# stokes_polarimeter.net
KiCad netlist of a schematic drawn in EAGLE
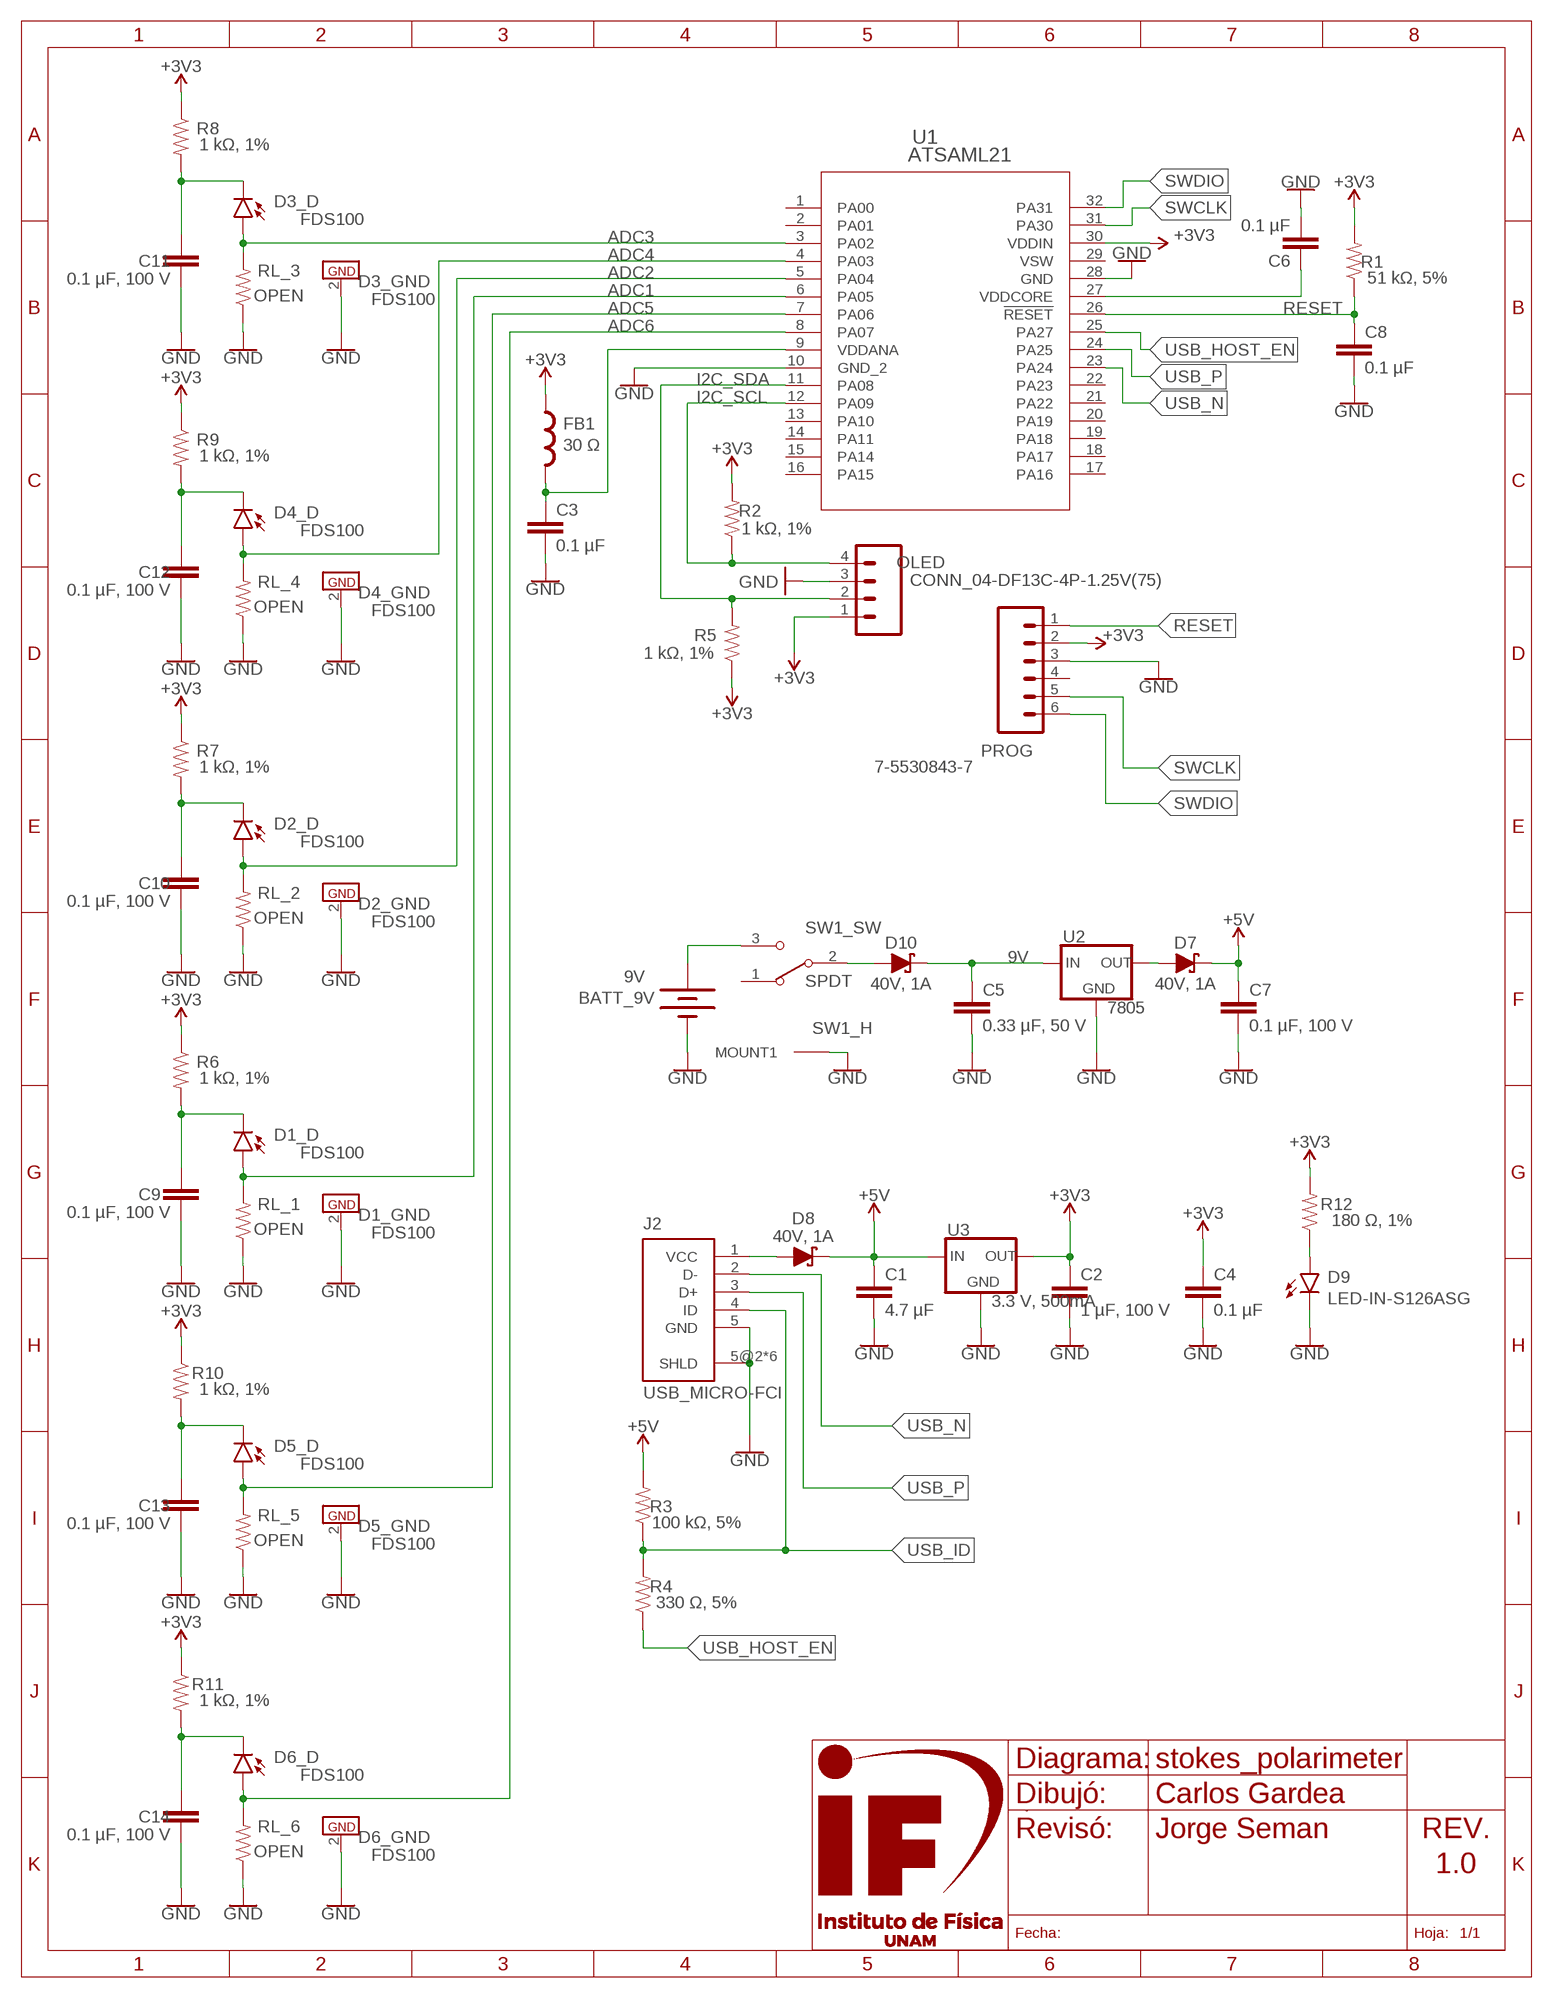
[diagram p0: schematic, sheet 1]

(export (version "E")
  (design (tool "Eeschema 10.0.6"))
  (components
    (comp (ref "BATT_9V")
      (value "9V")
      (footprint "eagle-import:5331")
      (fields (field (name "MFR") "Keystone Electronics"))
      (libsource (lib "eagle-import") (part "9V_BATTERY-5331"))
    )
    (comp (ref "C1")
      (value "4.7 µF")
      (footprint "eagle-import:C1206")
      (fields (field (name "MFR") "KEMET"))
      (libsource (lib "eagle-import") (part "4.7µF-C1206C475K3PACTU"))
    )
    (comp (ref "C2")
      (value "1 µF, 100 V")
      (footprint "eagle-import:C1206")
      (fields (field (name "MFR") "KEMET"))
      (libsource (lib "eagle-import") (part "1µF-C1206X105J1RACTU"))
    )
    (comp (ref "C3")
      (value "0.1 µF")
      (footprint "eagle-import:C1206")
      (fields (field (name "MFR") "KEMET"))
      (libsource (lib "eagle-import") (part "0.1µF-C1206C104J1RACTU"))
    )
    (comp (ref "C4")
      (value "0.1 µF")
      (footprint "eagle-import:C1206")
      (fields (field (name "MFR") "KEMET"))
      (libsource (lib "eagle-import") (part "0.1µF-C1206C104J1RACTU"))
    )
    (comp (ref "C5")
      (value "0.33 µF, 50 V")
      (footprint "eagle-import:C1206")
      (fields (field (name "MFR") "Samsung Electro-Mechanics"))
      (libsource (lib "eagle-import") (part "0.33µF-CL31B334KBFNNNE"))
    )
    (comp (ref "C6")
      (value "0.1 µF")
      (footprint "eagle-import:C1206")
      (fields (field (name "MFR") "KEMET"))
      (libsource (lib "eagle-import") (part "0.1µF-C1206C104J1RACTU"))
    )
    (comp (ref "C7")
      (value "0.1 µF, 100 V")
      (footprint "eagle-import:C1206")
      (fields (field (name "MFR") "AVX"))
      (libsource (lib "eagle-import") (part "0.1µF-12061C104KAT2A"))
    )
    (comp (ref "C8")
      (value "0.1 µF")
      (footprint "eagle-import:C1206")
      (fields (field (name "MFR") "KEMET"))
      (libsource (lib "eagle-import") (part "0.1µF-C1206C104J1RACTU"))
    )
    (comp (ref "C9")
      (value "0.1 µF, 100 V")
      (footprint "eagle-import:C1206")
      (fields (field (name "MFR") "AVX"))
      (libsource (lib "eagle-import") (part "0.1µF-12061C104KAT2A"))
    )
    (comp (ref "C10")
      (value "0.1 µF, 100 V")
      (footprint "eagle-import:C1206")
      (fields (field (name "MFR") "AVX"))
      (libsource (lib "eagle-import") (part "0.1µF-12061C104KAT2A"))
    )
    (comp (ref "C11")
      (value "0.1 µF, 100 V")
      (footprint "eagle-import:C1206")
      (fields (field (name "MFR") "AVX"))
      (libsource (lib "eagle-import") (part "0.1µF-12061C104KAT2A"))
    )
    (comp (ref "C12")
      (value "0.1 µF, 100 V")
      (footprint "eagle-import:C1206")
      (fields (field (name "MFR") "AVX"))
      (libsource (lib "eagle-import") (part "0.1µF-12061C104KAT2A"))
    )
    (comp (ref "C13")
      (value "0.1 µF, 100 V")
      (footprint "eagle-import:C1206")
      (fields (field (name "MFR") "AVX"))
      (libsource (lib "eagle-import") (part "0.1µF-12061C104KAT2A"))
    )
    (comp (ref "C14")
      (value "0.1 µF, 100 V")
      (footprint "eagle-import:C1206")
      (fields (field (name "MFR") "AVX"))
      (libsource (lib "eagle-import") (part "0.1µF-12061C104KAT2A"))
    )
    (comp (ref "D1")
      (value "FDS100")
      (footprint "eagle-import:FDS100_VERT")
      (fields (field (name "MFR") "THORLABS"))
      (libsource (lib "eagle-import") (part "FDS100-VERT"))
    )
    (comp (ref "D2")
      (value "FDS100")
      (footprint "eagle-import:FDS100_VERT")
      (fields (field (name "MFR") "THORLABS"))
      (libsource (lib "eagle-import") (part "FDS100-VERT"))
    )
    (comp (ref "D3")
      (value "FDS100")
      (footprint "eagle-import:FDS100_VERT")
      (fields (field (name "MFR") "THORLABS"))
      (libsource (lib "eagle-import") (part "FDS100-VERT"))
    )
    (comp (ref "D4")
      (value "FDS100")
      (footprint "eagle-import:FDS100_VERT")
      (fields (field (name "MFR") "THORLABS"))
      (libsource (lib "eagle-import") (part "FDS100-VERT"))
    )
    (comp (ref "D5")
      (value "FDS100")
      (footprint "eagle-import:FDS100_VERT")
      (fields (field (name "MFR") "THORLABS"))
      (libsource (lib "eagle-import") (part "FDS100-VERT"))
    )
    (comp (ref "D6")
      (value "FDS100")
      (footprint "eagle-import:FDS100_VERT")
      (fields (field (name "MFR") "THORLABS"))
      (libsource (lib "eagle-import") (part "FDS100-VERT"))
    )
    (comp (ref "D7")
      (value "40V, 1A")
      (footprint "eagle-import:DO-214AC")
      (fields (field (name "MFR") "ROHM Semiconductor"))
      (libsource (lib "eagle-import") (part "DIODE_SCHOTTKY-RB160L-40TE25"))
    )
    (comp (ref "D8")
      (value "40V, 1A")
      (footprint "eagle-import:DO-214AC")
      (fields (field (name "MFR") "ROHM Semiconductor"))
      (libsource (lib "eagle-import") (part "DIODE_SCHOTTKY-RB160L-40TE25"))
    )
    (comp (ref "D9")
      (value "LED-IN-S126ASG")
      (footprint "eagle-import:IN-S126AS")
      (fields (field (name "MFR") "Inolux"))
      (libsource (lib "eagle-import") (part "LED-IN-S126ASG"))
    )
    (comp (ref "D10")
      (value "40V, 1A")
      (footprint "eagle-import:DO-214AC")
      (fields (field (name "MFR") "ROHM Semiconductor"))
      (libsource (lib "eagle-import") (part "DIODE_SCHOTTKY-RB160L-40TE25"))
    )
    (comp (ref "FB1")
      (value "30 Ω")
      (footprint "eagle-import:L1206")
      (fields (field (name "MFR") "Bussmann / Eaton"))
      (libsource (lib "eagle-import") (part "FERRITE-MFBM1V3216-300-R"))
    )
    (comp (ref "J2")
      (value "USB_MICRO-FCI")
      (footprint "eagle-import:10103594-0001LF_FCI")
      (fields (field (name "MFR") "Amphenol ICC (FCI)"))
      (libsource (lib "eagle-import") (part "USB_MICRO-FCI"))
    )
    (comp (ref "OLED")
      (value "CONN_04-DF13C-4P-1.25V(75)")
      (footprint "eagle-import:DF13C4P125V")
      (fields (field (name "MFR") "Hirose Connector"))
      (libsource (lib "eagle-import") (part "CONN_04-DF13C-4P-1.25V(75)"))
    )
    (comp (ref "PROG")
      (value "7-5530843-7")
      (footprint "eagle-import:7-5530843-7")
      (fields (field (name "MFR") "TE Connectivity"))
      (libsource (lib "eagle-import") (part "EDGE_06"))
    )
    (comp (ref "R1")
      (value "51 kΩ, 5%")
      (footprint "eagle-import:R1206")
      (fields (field (name "MFR") "Stackpole Electronics Inc"))
      (libsource (lib "eagle-import") (part "51KΩ-RMCF1206JT51K0"))
    )
    (comp (ref "R2")
      (value "1 kΩ, 1%")
      (footprint "eagle-import:R1206")
      (fields (field (name "MFR") "Yageo"))
      (libsource (lib "eagle-import") (part "1KΩ-RC1206FR-071KL"))
    )
    (comp (ref "R3")
      (value "100 kΩ, 5%")
      (footprint "eagle-import:R1206")
      (fields (field (name "MFR") "YAGEO"))
      (libsource (lib "eagle-import") (part "100KΩ-RC1206JR-07100KL"))
    )
    (comp (ref "R4")
      (value "330 Ω, 5%")
      (footprint "eagle-import:R1206")
      (fields (field (name "MFR") "Yageo"))
      (libsource (lib "eagle-import") (part "330Ω-RC1206JR-13330RL"))
    )
    (comp (ref "R5")
      (value "1 kΩ, 1%")
      (footprint "eagle-import:R1206")
      (fields (field (name "MFR") "Yageo"))
      (libsource (lib "eagle-import") (part "1KΩ-RC1206FR-071KL"))
    )
    (comp (ref "R6")
      (value "1 kΩ, 1%")
      (footprint "eagle-import:R1206")
      (fields (field (name "MFR") "Yageo"))
      (libsource (lib "eagle-import") (part "1KΩ-RC1206FR-071KL"))
    )
    (comp (ref "R7")
      (value "1 kΩ, 1%")
      (footprint "eagle-import:R1206")
      (fields (field (name "MFR") "Yageo"))
      (libsource (lib "eagle-import") (part "1KΩ-RC1206FR-071KL"))
    )
    (comp (ref "R8")
      (value "1 kΩ, 1%")
      (footprint "eagle-import:R1206")
      (fields (field (name "MFR") "Yageo"))
      (libsource (lib "eagle-import") (part "1KΩ-RC1206FR-071KL"))
    )
    (comp (ref "R9")
      (value "1 kΩ, 1%")
      (footprint "eagle-import:R1206")
      (fields (field (name "MFR") "Yageo"))
      (libsource (lib "eagle-import") (part "1KΩ-RC1206FR-071KL"))
    )
    (comp (ref "R10")
      (value "1 kΩ, 1%")
      (footprint "eagle-import:R1206")
      (fields (field (name "MFR") "Yageo"))
      (libsource (lib "eagle-import") (part "1KΩ-RC1206FR-071KL"))
    )
    (comp (ref "R11")
      (value "1 kΩ, 1%")
      (footprint "eagle-import:R1206")
      (fields (field (name "MFR") "Yageo"))
      (libsource (lib "eagle-import") (part "1KΩ-RC1206FR-071KL"))
    )
    (comp (ref "R12")
      (value "180 Ω, 1%")
      (footprint "eagle-import:R1206")
      (fields (field (name "MFR") "Yageo"))
      (libsource (lib "eagle-import") (part "180Ω-RC1206FR-07180RL"))
    )
    (comp (ref "RL_1")
      (value "OPEN")
      (footprint "eagle-import:R1206_OPEN")
      (fields (field (name "MFR") "NA"))
      (libsource (lib "eagle-import") (part "OPEN-1206"))
    )
    (comp (ref "RL_2")
      (value "OPEN")
      (footprint "eagle-import:R1206_OPEN")
      (fields (field (name "MFR") "NA"))
      (libsource (lib "eagle-import") (part "OPEN-1206"))
    )
    (comp (ref "RL_3")
      (value "OPEN")
      (footprint "eagle-import:R1206_OPEN")
      (fields (field (name "MFR") "NA"))
      (libsource (lib "eagle-import") (part "OPEN-1206"))
    )
    (comp (ref "RL_4")
      (value "OPEN")
      (footprint "eagle-import:R1206_OPEN")
      (fields (field (name "MFR") "NA"))
      (libsource (lib "eagle-import") (part "OPEN-1206"))
    )
    (comp (ref "RL_5")
      (value "OPEN")
      (footprint "eagle-import:R1206_OPEN")
      (fields (field (name "MFR") "NA"))
      (libsource (lib "eagle-import") (part "OPEN-1206"))
    )
    (comp (ref "RL_6")
      (value "OPEN")
      (footprint "eagle-import:R1206_OPEN")
      (fields (field (name "MFR") "NA"))
      (libsource (lib "eagle-import") (part "OPEN-1206"))
    )
    (comp (ref "SW1")
      (value "SPDT")
      (footprint "eagle-import:SK12F17G7")
      (fields (field (name "MFR") "C&K"))
      (libsource (lib "eagle-import") (part "SK12F17G7-SK12F17G7"))
    )
    (comp (ref "U$54")
      (value "IFUNAM_FRAME_LETTER_VNONE")
      (footprint "eagle-import:NONE")
      (fields
        (field (name "AUTHOR") "Carlos Gardea")
        (field (name "REVISOR") "Jorge Seman")
        (field (name "author") "author")
      )
      (libsource (lib "eagle-import") (part "IFUNAM_FRAME_LETTER_VNONE"))
    )
    (comp (ref "U1")
      (value "ATSAML21")
      (footprint "eagle-import:TQFP32")
      (fields (field (name "MFR") "Microchip Technology / Atmel"))
      (libsource (lib "eagle-import") (part "ATSAML21-ATSAML21E16B-ANT"))
    )
    (comp (ref "U2")
      (value "7805")
      (footprint "eagle-import:DPAK")
      (fields (field (name "MFR") "STMicroelectronics"))
      (libsource (lib "eagle-import") (part "MC7805CT-L7805CDT-TR"))
    )
    (comp (ref "U3")
      (value "3.3 V, 500mA")
      (footprint "eagle-import:SOT223")
      (fields (field (name "MFR") "Microchip Technology"))
      (libsource (lib "eagle-import") (part "MCP1825-MCP1825S-3302E/DB"))
    )
  )
  (nets
    (net (code "1") (name "+3V3") (class "Default")
      (node (ref "C2") (pin "1") (pinfunction "1_1") (pintype "passive"))
      (node (ref "C4") (pin "1") (pinfunction "1_1") (pintype "passive"))
      (node (ref "FB1") (pin "1") (pinfunction "1_1") (pintype "passive"))
      (node (ref "OLED") (pin "1") (pinfunction "1_1") (pintype "passive"))
      (node (ref "PROG") (pin "2") (pinfunction "2_2") (pintype "passive"))
      (node (ref "R1") (pin "2") (pinfunction "2_2") (pintype "passive"))
      (node (ref "R10") (pin "1") (pinfunction "1_1") (pintype "passive"))
      (node (ref "R11") (pin "1") (pinfunction "1_1") (pintype "passive"))
      (node (ref "R12") (pin "2") (pinfunction "2_2") (pintype "passive"))
      (node (ref "R2") (pin "2") (pinfunction "2_2") (pintype "passive"))
      (node (ref "R5") (pin "1") (pinfunction "1_1") (pintype "passive"))
      (node (ref "R6") (pin "1") (pinfunction "1_1") (pintype "passive"))
      (node (ref "R7") (pin "1") (pinfunction "1_1") (pintype "passive"))
      (node (ref "R8") (pin "1") (pinfunction "1_1") (pintype "passive"))
      (node (ref "R9") (pin "1") (pinfunction "1_1") (pintype "passive"))
      (node (ref "U1") (pin "30") (pinfunction "VDDIN_30") (pintype "power_in"))
      (node (ref "U3") (pin "3") (pinfunction "OUT_3") (pintype "passive"))
    )
    (net (code "2") (name "+5V") (class "Default")
      (node (ref "C1") (pin "1") (pinfunction "1_1") (pintype "passive"))
      (node (ref "C7") (pin "1") (pinfunction "1_1") (pintype "passive"))
      (node (ref "D7") (pin "K") (pinfunction "C_K") (pintype "passive"))
      (node (ref "D8") (pin "K") (pinfunction "C_K") (pintype "passive"))
      (node (ref "R3") (pin "2") (pinfunction "2_2") (pintype "passive"))
      (node (ref "U3") (pin "1") (pinfunction "IN_1") (pintype "input"))
    )
    (net (code "3") (name "/9V") (class "Default")
      (node (ref "C5") (pin "1") (pinfunction "1_1") (pintype "passive"))
      (node (ref "D10") (pin "K") (pinfunction "C_K") (pintype "passive"))
      (node (ref "U2") (pin "1") (pinfunction "IN_1") (pintype "input"))
    )
    (net (code "4") (name "/ADC1") (class "Default")
      (node (ref "D1") (pin "1") (pinfunction "A_1") (pintype "passive"))
      (node (ref "RL_1") (pin "2") (pinfunction "2_2") (pintype "passive"))
      (node (ref "U1") (pin "6") (pinfunction "PA05_6") (pintype "bidirectional"))
    )
    (net (code "5") (name "/ADC2") (class "Default")
      (node (ref "D2") (pin "1") (pinfunction "A_1") (pintype "passive"))
      (node (ref "RL_2") (pin "2") (pinfunction "2_2") (pintype "passive"))
      (node (ref "U1") (pin "5") (pinfunction "PA04_5") (pintype "bidirectional"))
    )
    (net (code "6") (name "/ADC3") (class "Default")
      (node (ref "D3") (pin "1") (pinfunction "A_1") (pintype "passive"))
      (node (ref "RL_3") (pin "2") (pinfunction "2_2") (pintype "passive"))
      (node (ref "U1") (pin "3") (pinfunction "PA02_3") (pintype "bidirectional"))
    )
    (net (code "7") (name "/ADC4") (class "Default")
      (node (ref "D4") (pin "1") (pinfunction "A_1") (pintype "passive"))
      (node (ref "RL_4") (pin "2") (pinfunction "2_2") (pintype "passive"))
      (node (ref "U1") (pin "4") (pinfunction "PA03_4") (pintype "bidirectional"))
    )
    (net (code "8") (name "/ADC5") (class "Default")
      (node (ref "D5") (pin "1") (pinfunction "A_1") (pintype "passive"))
      (node (ref "RL_5") (pin "2") (pinfunction "2_2") (pintype "passive"))
      (node (ref "U1") (pin "7") (pinfunction "PA06_7") (pintype "bidirectional"))
    )
    (net (code "9") (name "/ADC6") (class "Default")
      (node (ref "D6") (pin "1") (pinfunction "A_1") (pintype "passive"))
      (node (ref "RL_6") (pin "2") (pinfunction "2_2") (pintype "passive"))
      (node (ref "U1") (pin "8") (pinfunction "PA07_8") (pintype "bidirectional"))
    )
    (net (code "10") (name "/I2C_SCL") (class "Default")
      (node (ref "OLED") (pin "4") (pinfunction "4_4") (pintype "passive"))
      (node (ref "R2") (pin "1") (pinfunction "1_1") (pintype "passive"))
      (node (ref "U1") (pin "12") (pinfunction "PA09_12") (pintype "bidirectional"))
    )
    (net (code "11") (name "/I2C_SDA") (class "Default")
      (node (ref "OLED") (pin "2") (pinfunction "2_2") (pintype "passive"))
      (node (ref "R5") (pin "2") (pinfunction "2_2") (pintype "passive"))
      (node (ref "U1") (pin "11") (pinfunction "PA08_11") (pintype "bidirectional"))
    )
    (net (code "12") (name "GND") (class "Default")
      (node (ref "BATT_9V") (pin "-") (pinfunction "-_-") (pintype "power_in"))
      (node (ref "C1") (pin "2") (pinfunction "2_2") (pintype "passive"))
      (node (ref "C10") (pin "2") (pinfunction "2_2") (pintype "passive"))
      (node (ref "C11") (pin "2") (pinfunction "2_2") (pintype "passive"))
      (node (ref "C12") (pin "2") (pinfunction "2_2") (pintype "passive"))
      (node (ref "C13") (pin "2") (pinfunction "2_2") (pintype "passive"))
      (node (ref "C14") (pin "2") (pinfunction "2_2") (pintype "passive"))
      (node (ref "C2") (pin "2") (pinfunction "2_2") (pintype "passive"))
      (node (ref "C3") (pin "2") (pinfunction "2_2") (pintype "passive"))
      (node (ref "C4") (pin "2") (pinfunction "2_2") (pintype "passive"))
      (node (ref "C5") (pin "2") (pinfunction "2_2") (pintype "passive"))
      (node (ref "C6") (pin "2") (pinfunction "2_2") (pintype "passive"))
      (node (ref "C7") (pin "2") (pinfunction "2_2") (pintype "passive"))
      (node (ref "C8") (pin "2") (pinfunction "2_2") (pintype "passive"))
      (node (ref "C9") (pin "2") (pinfunction "2_2") (pintype "passive"))
      (node (ref "D1") (pin "2") (pinfunction "P$GND_2") (pintype "bidirectional"))
      (node (ref "D2") (pin "2") (pinfunction "P$GND_2") (pintype "bidirectional"))
      (node (ref "D3") (pin "2") (pinfunction "P$GND_2") (pintype "bidirectional"))
      (node (ref "D4") (pin "2") (pinfunction "P$GND_2") (pintype "bidirectional"))
      (node (ref "D5") (pin "2") (pinfunction "P$GND_2") (pintype "bidirectional"))
      (node (ref "D6") (pin "2") (pinfunction "P$GND_2") (pintype "bidirectional"))
      (node (ref "D9") (pin "K") (pinfunction "C_K") (pintype "passive"))
      (node (ref "J2") (pin "5") (pinfunction "GND_5") (pintype "passive"))
      (node (ref "J2") (pin "5@2") (pinfunction "SHLD_5@2") (pintype "passive"))
      (node (ref "J2") (pin "5@3") (pinfunction "SHLD_5@3") (pintype "passive"))
      (node (ref "J2") (pin "5@4") (pinfunction "SHLD_5@4") (pintype "passive"))
      (node (ref "J2") (pin "5@5") (pinfunction "SHLD_5@5") (pintype "passive"))
      (node (ref "J2") (pin "5@6") (pinfunction "SHLD_5@6") (pintype "passive"))
      (node (ref "J2") (pin "5@7") (pinfunction "SHLD_5@7") (pintype "passive"))
      (node (ref "OLED") (pin "3") (pinfunction "3_3") (pintype "passive"))
      (node (ref "PROG") (pin "3") (pinfunction "3_3") (pintype "passive"))
      (node (ref "RL_1") (pin "1") (pinfunction "1_1") (pintype "passive"))
      (node (ref "RL_2") (pin "1") (pinfunction "1_1") (pintype "passive"))
      (node (ref "RL_3") (pin "1") (pinfunction "1_1") (pintype "passive"))
      (node (ref "RL_4") (pin "1") (pinfunction "1_1") (pintype "passive"))
      (node (ref "RL_5") (pin "1") (pinfunction "1_1") (pintype "passive"))
      (node (ref "RL_6") (pin "1") (pinfunction "1_1") (pintype "passive"))
      (node (ref "SW1") (pin "MH1") (pinfunction "MOUNT1_MH1") (pintype "passive"))
      (node (ref "SW1") (pin "MH2") (pinfunction "MOUNT1_MH2") (pintype "passive"))
      (node (ref "SW1") (pin "MH3") (pinfunction "MOUNT1_MH3") (pintype "passive"))
      (node (ref "SW1") (pin "MH4") (pinfunction "MOUNT1_MH4") (pintype "passive"))
      (node (ref "U1") (pin "10") (pinfunction "GND_2_10") (pintype "passive"))
      (node (ref "U1") (pin "28") (pinfunction "GND_28") (pintype "passive"))
      (node (ref "U2") (pin "4") (pinfunction "GND_4") (pintype "input"))
      (node (ref "U3") (pin "2") (pinfunction "GND_2") (pintype "input"))
      (node (ref "U3") (pin "4") (pinfunction "GND_4") (pintype "input"))
    )
    (net (code "13") (name "Net-(D1A-C)") (class "Default")
      (node (ref "C9") (pin "1") (pinfunction "1_1") (pintype "passive"))
      (node (ref "D1") (pin "3") (pinfunction "C_3") (pintype "passive"))
      (node (ref "R6") (pin "2") (pinfunction "2_2") (pintype "passive"))
    )
    (net (code "14") (name "Net-(D2A-C)") (class "Default")
      (node (ref "C10") (pin "1") (pinfunction "1_1") (pintype "passive"))
      (node (ref "D2") (pin "3") (pinfunction "C_3") (pintype "passive"))
      (node (ref "R7") (pin "2") (pinfunction "2_2") (pintype "passive"))
    )
    (net (code "15") (name "Net-(D3A-C)") (class "Default")
      (node (ref "C11") (pin "1") (pinfunction "1_1") (pintype "passive"))
      (node (ref "D3") (pin "3") (pinfunction "C_3") (pintype "passive"))
      (node (ref "R8") (pin "2") (pinfunction "2_2") (pintype "passive"))
    )
    (net (code "16") (name "Net-(D4A-C)") (class "Default")
      (node (ref "C12") (pin "1") (pinfunction "1_1") (pintype "passive"))
      (node (ref "D4") (pin "3") (pinfunction "C_3") (pintype "passive"))
      (node (ref "R9") (pin "2") (pinfunction "2_2") (pintype "passive"))
    )
    (net (code "17") (name "Net-(D5A-C)") (class "Default")
      (node (ref "C13") (pin "1") (pinfunction "1_1") (pintype "passive"))
      (node (ref "D5") (pin "3") (pinfunction "C_3") (pintype "passive"))
      (node (ref "R10") (pin "2") (pinfunction "2_2") (pintype "passive"))
    )
    (net (code "18") (name "Net-(D6A-C)") (class "Default")
      (node (ref "C14") (pin "1") (pinfunction "1_1") (pintype "passive"))
      (node (ref "D6") (pin "3") (pinfunction "C_3") (pintype "passive"))
      (node (ref "R11") (pin "2") (pinfunction "2_2") (pintype "passive"))
    )
    (net (code "19") (name "Net-(D9-PadA)") (class "Default")
      (node (ref "D9") (pin "A") (pinfunction "A_A") (pintype "passive"))
      (node (ref "R12") (pin "1") (pinfunction "1_1") (pintype "passive"))
    )
    (net (code "20") (name "Net-(J2-VCC)") (class "Default")
      (node (ref "D8") (pin "A") (pinfunction "A_A") (pintype "passive"))
      (node (ref "J2") (pin "1") (pinfunction "VCC_1") (pintype "passive"))
    )
    (net (code "21") (name "Net-(SW1B-COMMON)") (class "Default")
      (node (ref "D10") (pin "A") (pinfunction "A_A") (pintype "passive"))
      (node (ref "SW1") (pin "2") (pinfunction "COMMON_2") (pintype "passive"))
    )
    (net (code "22") (name "Net-(SW1B-NO)") (class "Default")
      (node (ref "BATT_9V") (pin "+") (pinfunction "+_+") (pintype "power_in"))
      (node (ref "SW1") (pin "3") (pinfunction "NO_3") (pintype "passive"))
    )
    (net (code "23") (name "Net-(U1-VDDANA)") (class "Default")
      (node (ref "C3") (pin "1") (pinfunction "1_1") (pintype "passive"))
      (node (ref "FB1") (pin "2") (pinfunction "2_2") (pintype "passive"))
      (node (ref "U1") (pin "9") (pinfunction "VDDANA_9") (pintype "power_in"))
    )
    (net (code "24") (name "Net-(U1-VDDCORE)") (class "Default")
      (node (ref "C6") (pin "1") (pinfunction "1_1") (pintype "passive"))
      (node (ref "U1") (pin "27") (pinfunction "VDDCORE_27") (pintype "power_in"))
    )
    (net (code "25") (name "Net-(U2-OUT)") (class "Default")
      (node (ref "D7") (pin "A") (pinfunction "A_A") (pintype "passive"))
      (node (ref "U2") (pin "3") (pinfunction "OUT_3") (pintype "passive"))
    )
    (net (code "26") (name "RESET") (class "Default")
      (node (ref "C8") (pin "1") (pinfunction "1_1") (pintype "passive"))
      (node (ref "PROG") (pin "1") (pinfunction "1_1") (pintype "passive"))
      (node (ref "R1") (pin "1") (pinfunction "1_1") (pintype "passive"))
      (node (ref "U1") (pin "26") (pinfunction "~{RESET}_26") (pintype "passive"))
    )
    (net (code "27") (name "SWCLK") (class "Default")
      (node (ref "PROG") (pin "5") (pinfunction "5_5") (pintype "passive"))
      (node (ref "U1") (pin "31") (pinfunction "PA30_31") (pintype "bidirectional"))
    )
    (net (code "28") (name "SWDIO") (class "Default")
      (node (ref "PROG") (pin "6") (pinfunction "6_6") (pintype "passive"))
      (node (ref "U1") (pin "32") (pinfunction "PA31_32") (pintype "bidirectional"))
    )
    (net (code "29") (name "USB_HOST_EN") (class "Default")
      (node (ref "R4") (pin "1") (pinfunction "1_1") (pintype "passive"))
      (node (ref "U1") (pin "25") (pinfunction "PA27_25") (pintype "bidirectional"))
    )
    (net (code "30") (name "USB_ID") (class "Default")
      (node (ref "J2") (pin "4") (pinfunction "ID_4") (pintype "bidirectional"))
      (node (ref "R3") (pin "1") (pinfunction "1_1") (pintype "passive"))
      (node (ref "R4") (pin "2") (pinfunction "2_2") (pintype "passive"))
    )
    (net (code "31") (name "USB_N") (class "Default")
      (node (ref "J2") (pin "2") (pinfunction "D-_2") (pintype "bidirectional"))
      (node (ref "U1") (pin "23") (pinfunction "PA24_23") (pintype "bidirectional"))
    )
    (net (code "32") (name "USB_P") (class "Default")
      (node (ref "J2") (pin "3") (pinfunction "D+_3") (pintype "bidirectional"))
      (node (ref "U1") (pin "24") (pinfunction "PA25_24") (pintype "bidirectional"))
    )
    (net (code "33") (name "unconnected-(PROG-Pad4)") (class "Default")
      (node (ref "PROG") (pin "4") (pinfunction "4_4") (pintype "passive"))
    )
    (net (code "34") (name "unconnected-(SW1B-NC-Pad1)") (class "Default")
      (node (ref "SW1") (pin "1") (pinfunction "NC_1") (pintype "passive"))
    )
    (net (code "35") (name "unconnected-(U1-PA00-Pad1)") (class "Default")
      (node (ref "U1") (pin "1") (pinfunction "PA00_1") (pintype "bidirectional"))
    )
    (net (code "36") (name "unconnected-(U1-PA01-Pad2)") (class "Default")
      (node (ref "U1") (pin "2") (pinfunction "PA01_2") (pintype "bidirectional"))
    )
    (net (code "37") (name "unconnected-(U1-PA10-Pad13)") (class "Default")
      (node (ref "U1") (pin "13") (pinfunction "PA10_13") (pintype "bidirectional"))
    )
    (net (code "38") (name "unconnected-(U1-PA11-Pad14)") (class "Default")
      (node (ref "U1") (pin "14") (pinfunction "PA11_14") (pintype "bidirectional"))
    )
    (net (code "39") (name "unconnected-(U1-PA14-Pad15)") (class "Default")
      (node (ref "U1") (pin "15") (pinfunction "PA14_15") (pintype "bidirectional"))
    )
    (net (code "40") (name "unconnected-(U1-PA15-Pad16)") (class "Default")
      (node (ref "U1") (pin "16") (pinfunction "PA15_16") (pintype "bidirectional"))
    )
    (net (code "41") (name "unconnected-(U1-PA16-Pad17)") (class "Default")
      (node (ref "U1") (pin "17") (pinfunction "PA16_17") (pintype "bidirectional"))
    )
    (net (code "42") (name "unconnected-(U1-PA17-Pad18)") (class "Default")
      (node (ref "U1") (pin "18") (pinfunction "PA17_18") (pintype "bidirectional"))
    )
    (net (code "43") (name "unconnected-(U1-PA18-Pad19)") (class "Default")
      (node (ref "U1") (pin "19") (pinfunction "PA18_19") (pintype "bidirectional"))
    )
    (net (code "44") (name "unconnected-(U1-PA19-Pad20)") (class "Default")
      (node (ref "U1") (pin "20") (pinfunction "PA19_20") (pintype "bidirectional"))
    )
    (net (code "45") (name "unconnected-(U1-PA22-Pad21)") (class "Default")
      (node (ref "U1") (pin "21") (pinfunction "PA22_21") (pintype "bidirectional"))
    )
    (net (code "46") (name "unconnected-(U1-PA23-Pad22)") (class "Default")
      (node (ref "U1") (pin "22") (pinfunction "PA23_22") (pintype "bidirectional"))
    )
    (net (code "47") (name "unconnected-(U1-VSW-Pad29)") (class "Default")
      (node (ref "U1") (pin "29") (pinfunction "VSW_29") (pintype "passive"))
    )
  )
)
